# AVR_Roller_PCB_7x.net
KiCad netlist of a schematic drawn in EAGLE
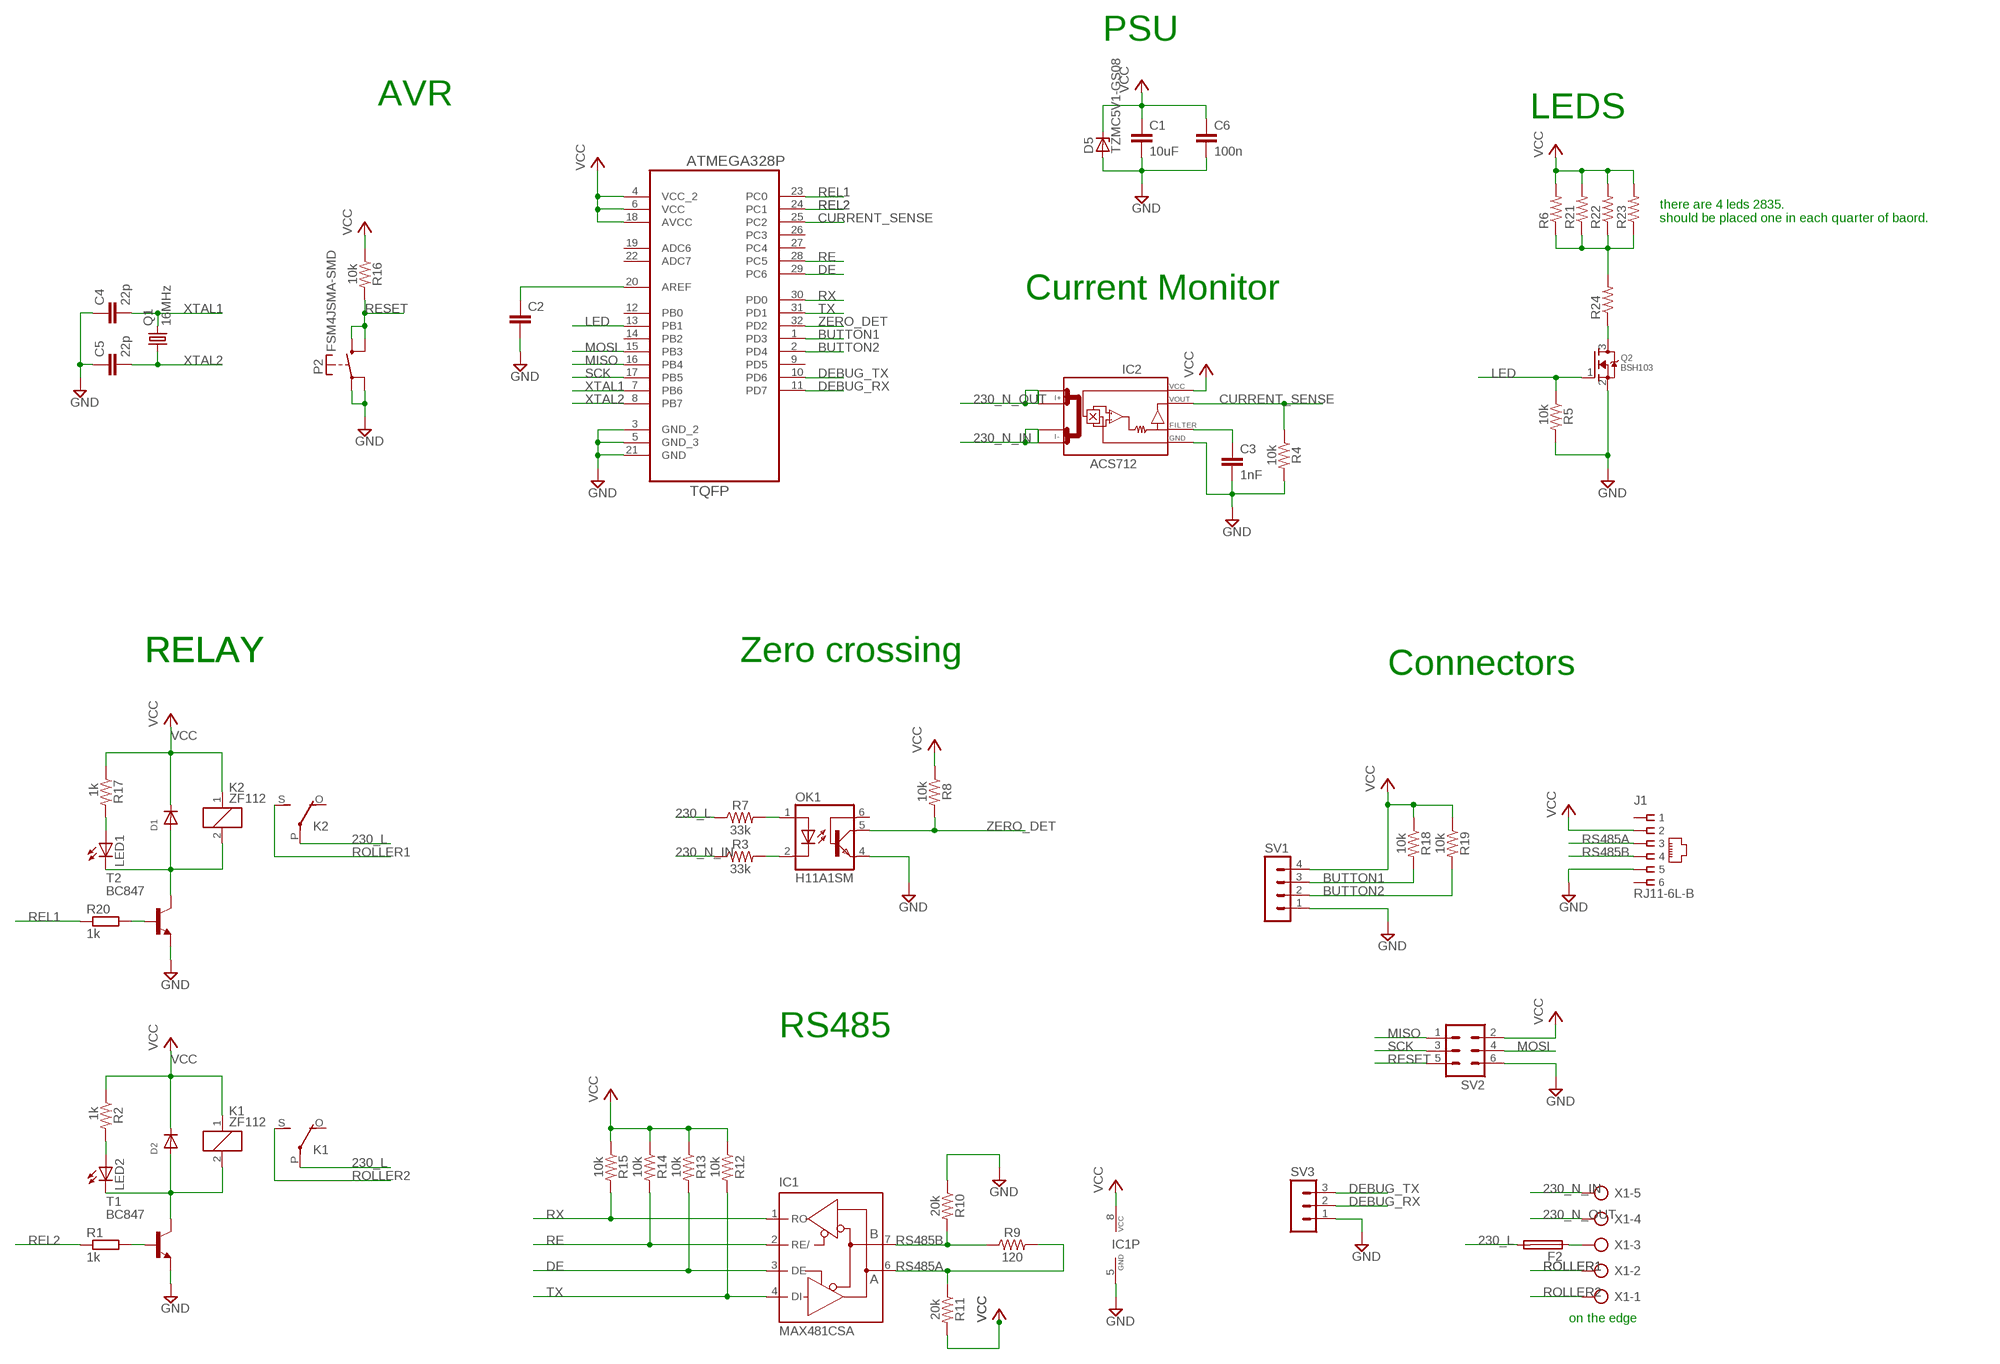
[diagram p0: schematic, sheet 1]

(export (version "E")
  (design (tool "Eeschema 10.0.6"))
  (components
    (comp (ref "C1")
      (value "10uF")
      (footprint "eagle-import:1206")
      (libsource (lib "eagle-import") (part "10UF-1206-6.3V-20%"))
    )
    (comp (ref "C2")
      (value "C-EUC0805K")
      (footprint "eagle-import:C0805K")
      (libsource (lib "eagle-import") (part "C-EUC0805K"))
    )
    (comp (ref "C3")
      (value "1nF")
      (footprint "eagle-import:C0805K")
      (libsource (lib "eagle-import") (part "C-EUC0805K"))
    )
    (comp (ref "C4")
      (value "22p")
      (footprint "eagle-import:C0805K")
      (libsource (lib "eagle-import") (part "C-EUC0805K"))
    )
    (comp (ref "C5")
      (value "22p")
      (footprint "eagle-import:C0805K")
      (libsource (lib "eagle-import") (part "C-EUC0805K"))
    )
    (comp (ref "C6")
      (value "100n")
      (footprint "eagle-import:C0805K")
      (libsource (lib "eagle-import") (part "C-EUC0805K"))
    )
    (comp (ref "D1")
      (value "DIODE_SOD-123FL")
      (footprint "eagle-import:SOD-123FL")
      (libsource (lib "eagle-import") (part "DIODE_SOD-123FL"))
    )
    (comp (ref "D2")
      (value "DIODE_SOD-123FL")
      (footprint "eagle-import:SOD-123FL")
      (libsource (lib "eagle-import") (part "DIODE_SOD-123FL"))
    )
    (comp (ref "D5")
      (value "TZMC5V1-GS08")
      (footprint "eagle-import:SOD80C")
      (libsource (lib "eagle-import") (part "ZENER-DIODESOD80C"))
    )
    (comp (ref "F2")
      (value "TE5")
      (footprint "eagle-import:TE5")
      (libsource (lib "eagle-import") (part "TE5"))
    )
    (comp (ref "IC1")
      (value "MAX481CSA")
      (footprint "eagle-import:SO08")
      (fields (field (name "MF") "MAXIM"))
      (libsource (lib "eagle-import") (part "MAX481CSA"))
    )
    (comp (ref "IC2")
      (value "ACS712")
      (footprint "eagle-import:SO08")
      (libsource (lib "eagle-import") (part "ACS712"))
    )
    (comp (ref "J1")
      (value "RJ11-6L-B")
      (footprint "eagle-import:RJ11-NO_SHIELD")
      (fields (field (name "MF") "TYCO ELECTRONICS"))
      (libsource (lib "eagle-import") (part "RJ11-6L-B"))
    )
    (comp (ref "K1")
      (value "ZF112")
      (footprint "eagle-import:ZF112")
      (libsource (lib "eagle-import") (part "ZF112"))
    )
    (comp (ref "K2")
      (value "ZF112")
      (footprint "eagle-import:ZF112")
      (libsource (lib "eagle-import") (part "ZF112"))
    )
    (comp (ref "LED1")
      (value "LEDCHIPLED_0805")
      (footprint "eagle-import:CHIPLED_0805")
      (libsource (lib "eagle-import") (part "LEDCHIPLED_0805"))
    )
    (comp (ref "LED2")
      (value "LEDCHIPLED_0805")
      (footprint "eagle-import:CHIPLED_0805")
      (libsource (lib "eagle-import") (part "LEDCHIPLED_0805"))
    )
    (comp (ref "OK1")
      (value "H11A1SM")
      (footprint "eagle-import:DIL6-SMD")
      (libsource (lib "eagle-import") (part "H11A?MS1"))
    )
    (comp (ref "P2")
      (value "FSM4JSMA-SMD")
      (footprint "eagle-import:FSM4JSMA-SMD")
      (libsource (lib "eagle-import") (part "FSM4JSMA-SMD"))
    )
    (comp (ref "Q1")
      (value "16MHz")
      (footprint "eagle-import:CSM-7X-DU")
      (libsource (lib "eagle-import") (part "CSM-7X-DU"))
    )
    (comp (ref "Q2")
      (value "BSH103")
      (footprint "eagle-import:SOT23")
      (libsource (lib "eagle-import") (part "MOSFET-NREFLOW"))
    )
    (comp (ref "R1")
      (value "1k")
      (footprint "eagle-import:M0805")
      (libsource (lib "eagle-import") (part "R-EU_M0805"))
    )
    (comp (ref "R2")
      (value "1k")
      (footprint "eagle-import:0805")
      (libsource (lib "eagle-import") (part "RESISTOR0805"))
    )
    (comp (ref "R3")
      (value "33k")
      (footprint "eagle-import:1210")
      (libsource (lib "eagle-import") (part "0.1OHM-1210-1/2W-1%"))
    )
    (comp (ref "R4")
      (value "10k")
      (footprint "eagle-import:0805")
      (libsource (lib "eagle-import") (part "RESISTOR0805"))
    )
    (comp (ref "R5")
      (value "10k")
      (footprint "eagle-import:0805")
      (libsource (lib "eagle-import") (part "RESISTOR0805"))
    )
    (comp (ref "R6")
      (value "R-US_R1210")
      (footprint "eagle-import:R1210")
      (libsource (lib "eagle-import") (part "R-US_R1210"))
    )
    (comp (ref "R7")
      (value "33k")
      (footprint "eagle-import:1210")
      (libsource (lib "eagle-import") (part "0.1OHM-1210-1/2W-1%"))
    )
    (comp (ref "R8")
      (value "10k")
      (footprint "eagle-import:0805")
      (libsource (lib "eagle-import") (part "RESISTOR0805"))
    )
    (comp (ref "R9")
      (value "120")
      (footprint "eagle-import:0805")
      (libsource (lib "eagle-import") (part "RESISTOR0805"))
    )
    (comp (ref "R10")
      (value "20k")
      (footprint "eagle-import:0805")
      (libsource (lib "eagle-import") (part "RESISTOR0805"))
    )
    (comp (ref "R11")
      (value "20k")
      (footprint "eagle-import:0805")
      (libsource (lib "eagle-import") (part "RESISTOR0805"))
    )
    (comp (ref "R12")
      (value "10k")
      (footprint "eagle-import:0805")
      (libsource (lib "eagle-import") (part "RESISTOR0805"))
    )
    (comp (ref "R13")
      (value "10k")
      (footprint "eagle-import:0805")
      (libsource (lib "eagle-import") (part "RESISTOR0805"))
    )
    (comp (ref "R14")
      (value "10k")
      (footprint "eagle-import:0805")
      (libsource (lib "eagle-import") (part "RESISTOR0805"))
    )
    (comp (ref "R15")
      (value "10k")
      (footprint "eagle-import:0805")
      (libsource (lib "eagle-import") (part "RESISTOR0805"))
    )
    (comp (ref "R16")
      (value "10k")
      (footprint "eagle-import:0805")
      (libsource (lib "eagle-import") (part "RESISTOR0805"))
    )
    (comp (ref "R17")
      (value "1k")
      (footprint "eagle-import:0805")
      (libsource (lib "eagle-import") (part "RESISTOR0805"))
    )
    (comp (ref "R18")
      (value "10k")
      (footprint "eagle-import:0805")
      (libsource (lib "eagle-import") (part "RESISTOR0805"))
    )
    (comp (ref "R19")
      (value "10k")
      (footprint "eagle-import:0805")
      (libsource (lib "eagle-import") (part "RESISTOR0805"))
    )
    (comp (ref "R20")
      (value "1k")
      (footprint "eagle-import:M0805")
      (libsource (lib "eagle-import") (part "R-EU_M0805"))
    )
    (comp (ref "R21")
      (value "R-US_R1210")
      (footprint "eagle-import:R1210")
      (libsource (lib "eagle-import") (part "R-US_R1210"))
    )
    (comp (ref "R22")
      (value "R-US_R1210")
      (footprint "eagle-import:R1210")
      (libsource (lib "eagle-import") (part "R-US_R1210"))
    )
    (comp (ref "R23")
      (value "R-US_R1210")
      (footprint "eagle-import:R1210")
      (libsource (lib "eagle-import") (part "R-US_R1210"))
    )
    (comp (ref "R24")
      (value "R-US_R1210")
      (footprint "eagle-import:R1210")
      (libsource (lib "eagle-import") (part "R-US_R1210"))
    )
    (comp (ref "SV1")
      (value "MA04-1")
      (footprint "eagle-import:MA04-1")
      (libsource (lib "eagle-import") (part "MA04-1"))
    )
    (comp (ref "SV2")
      (value "MA03-2")
      (footprint "eagle-import:MA03-2")
      (libsource (lib "eagle-import") (part "MA03-2"))
    )
    (comp (ref "SV3")
      (value "MA03-1")
      (footprint "eagle-import:MA03-1")
      (libsource (lib "eagle-import") (part "MA03-1"))
    )
    (comp (ref "T1")
      (value "BC847")
      (footprint "eagle-import:SOT23")
      (libsource (lib "eagle-import") (part "BC847"))
    )
    (comp (ref "T2")
      (value "BC847")
      (footprint "eagle-import:SOT23")
      (libsource (lib "eagle-import") (part "BC847"))
    )
    (comp (ref "U1")
      (value "ATMEGA328P-AU")
      (footprint "eagle-import:QFP80P900X900X120-32N")
      (libsource (lib "eagle-import") (part "ATMEGA328P-AU"))
    )
    (comp (ref "X1")
      (value "AK300/5")
      (footprint "eagle-import:AK300_5")
      (libsource (lib "eagle-import") (part "AK300/5"))
    )
  )
  (nets
    (net (code "1") (name "/230_L") (class "Default")
      (node (ref "F2") (pin "2") (pinfunction "2_2") (pintype "passive"))
      (node (ref "K1") (pin "P") (pinfunction "P_P") (pintype "passive"))
      (node (ref "K2") (pin "P") (pinfunction "P_P") (pintype "passive"))
      (node (ref "R7") (pin "1") (pinfunction "1_1") (pintype "passive"))
    )
    (net (code "2") (name "/230_N_IN") (class "Default")
      (node (ref "IC2") (pin "3") (pinfunction "I-_0_3") (pintype "bidirectional"))
      (node (ref "IC2") (pin "4") (pinfunction "I-_1_4") (pintype "bidirectional"))
      (node (ref "R3") (pin "1") (pinfunction "1_1") (pintype "passive"))
      (node (ref "X1") (pin "5") (pinfunction "KL_5") (pintype "passive"))
    )
    (net (code "3") (name "/230_N_OUT") (class "Default")
      (node (ref "IC2") (pin "1") (pinfunction "I+_0_1") (pintype "bidirectional"))
      (node (ref "IC2") (pin "2") (pinfunction "I+_1_2") (pintype "bidirectional"))
      (node (ref "X1") (pin "4") (pinfunction "KL_4") (pintype "passive"))
    )
    (net (code "4") (name "/BUTTON1") (class "Default")
      (node (ref "R18") (pin "2") (pinfunction "2_2") (pintype "passive"))
      (node (ref "SV1") (pin "3") (pinfunction "3_3") (pintype "passive"))
      (node (ref "U1") (pin "1") (pinfunction "PD3_1") (pintype "bidirectional"))
    )
    (net (code "5") (name "/BUTTON2") (class "Default")
      (node (ref "R19") (pin "2") (pinfunction "2_2") (pintype "passive"))
      (node (ref "SV1") (pin "2") (pinfunction "2_2") (pintype "passive"))
      (node (ref "U1") (pin "2") (pinfunction "PD4_2") (pintype "bidirectional"))
    )
    (net (code "6") (name "/CURRENT_SENSE") (class "Default")
      (node (ref "IC2") (pin "7") (pinfunction "VOUT_7") (pintype "output"))
      (node (ref "R4") (pin "1") (pinfunction "1_1") (pintype "passive"))
      (node (ref "U1") (pin "25") (pinfunction "PC2_25") (pintype "bidirectional"))
    )
    (net (code "7") (name "/DE") (class "Default")
      (node (ref "IC1") (pin "3") (pinfunction "DE_3") (pintype "input"))
      (node (ref "R13") (pin "2") (pinfunction "2_2") (pintype "passive"))
      (node (ref "U1") (pin "29") (pinfunction "PC6_29") (pintype "bidirectional"))
    )
    (net (code "8") (name "/DEBUG_RX") (class "Default")
      (node (ref "SV3") (pin "2") (pinfunction "2_2") (pintype "passive"))
      (node (ref "U1") (pin "11") (pinfunction "PD7_11") (pintype "bidirectional"))
    )
    (net (code "9") (name "/DEBUG_TX") (class "Default")
      (node (ref "SV3") (pin "3") (pinfunction "3_3") (pintype "passive"))
      (node (ref "U1") (pin "10") (pinfunction "PD6_10") (pintype "bidirectional"))
    )
    (net (code "10") (name "/LED") (class "Default")
      (node (ref "Q2") (pin "1") (pinfunction "G_1") (pintype "bidirectional"))
      (node (ref "R5") (pin "1") (pinfunction "1_1") (pintype "passive"))
      (node (ref "U1") (pin "13") (pinfunction "PB1_13") (pintype "bidirectional"))
    )
    (net (code "11") (name "/MISO") (class "Default")
      (node (ref "SV2") (pin "1") (pinfunction "1_1") (pintype "passive"))
      (node (ref "U1") (pin "16") (pinfunction "PB4_16") (pintype "bidirectional"))
    )
    (net (code "12") (name "/MOSI") (class "Default")
      (node (ref "SV2") (pin "4") (pinfunction "4_4") (pintype "passive"))
      (node (ref "U1") (pin "15") (pinfunction "PB3_15") (pintype "bidirectional"))
    )
    (net (code "13") (name "/RE") (class "Default")
      (node (ref "IC1") (pin "2") (pinfunction "RE/_2") (pintype "input"))
      (node (ref "R14") (pin "2") (pinfunction "2_2") (pintype "passive"))
      (node (ref "U1") (pin "28") (pinfunction "PC5_28") (pintype "bidirectional"))
    )
    (net (code "14") (name "/REL1") (class "Default")
      (node (ref "R20") (pin "1") (pinfunction "1_1") (pintype "passive"))
      (node (ref "U1") (pin "23") (pinfunction "PC0_23") (pintype "bidirectional"))
    )
    (net (code "15") (name "/REL2") (class "Default")
      (node (ref "R1") (pin "1") (pinfunction "1_1") (pintype "passive"))
      (node (ref "U1") (pin "24") (pinfunction "PC1_24") (pintype "bidirectional"))
    )
    (net (code "16") (name "/RESET") (class "Default")
      (node (ref "P2") (pin "P$3") (pinfunction "S_P$3") (pintype "passive"))
      (node (ref "P2") (pin "P$4") (pinfunction "S_P$4") (pintype "passive"))
      (node (ref "R16") (pin "2") (pinfunction "2_2") (pintype "passive"))
      (node (ref "SV2") (pin "5") (pinfunction "5_5") (pintype "passive"))
    )
    (net (code "17") (name "/ROLLER1") (class "Default")
      (node (ref "K2") (pin "S") (pinfunction "S_S") (pintype "passive"))
      (node (ref "X1") (pin "2") (pinfunction "KL_2") (pintype "passive"))
    )
    (net (code "18") (name "/ROLLER2") (class "Default")
      (node (ref "K1") (pin "S") (pinfunction "S_S") (pintype "passive"))
      (node (ref "X1") (pin "1") (pinfunction "KL_1") (pintype "passive"))
    )
    (net (code "19") (name "/RS485A") (class "Default")
      (node (ref "IC1") (pin "6") (pinfunction "A_6") (pintype "passive"))
      (node (ref "J1") (pin "3") (pinfunction "3_3") (pintype "passive"))
      (node (ref "R11") (pin "1") (pinfunction "1_1") (pintype "passive"))
      (node (ref "R9") (pin "2") (pinfunction "2_2") (pintype "passive"))
    )
    (net (code "20") (name "/RS485B") (class "Default")
      (node (ref "IC1") (pin "7") (pinfunction "B_7") (pintype "passive"))
      (node (ref "J1") (pin "4") (pinfunction "4_4") (pintype "passive"))
      (node (ref "R10") (pin "2") (pinfunction "2_2") (pintype "passive"))
      (node (ref "R9") (pin "1") (pinfunction "1_1") (pintype "passive"))
    )
    (net (code "21") (name "/RX") (class "Default")
      (node (ref "IC1") (pin "1") (pinfunction "RO_1") (pintype "output"))
      (node (ref "R15") (pin "2") (pinfunction "2_2") (pintype "passive"))
      (node (ref "U1") (pin "30") (pinfunction "PD0_30") (pintype "bidirectional"))
    )
    (net (code "22") (name "/SCK") (class "Default")
      (node (ref "SV2") (pin "3") (pinfunction "3_3") (pintype "passive"))
      (node (ref "U1") (pin "17") (pinfunction "PB5_17") (pintype "bidirectional"))
    )
    (net (code "23") (name "/TX") (class "Default")
      (node (ref "IC1") (pin "4") (pinfunction "DI_4") (pintype "input"))
      (node (ref "R12") (pin "2") (pinfunction "2_2") (pintype "passive"))
      (node (ref "U1") (pin "31") (pinfunction "PD1_31") (pintype "bidirectional"))
    )
    (net (code "24") (name "/XTAL1") (class "Default")
      (node (ref "C4") (pin "2") (pinfunction "2_2") (pintype "passive"))
      (node (ref "Q1") (pin "2") (pinfunction "2_2") (pintype "passive"))
      (node (ref "U1") (pin "7") (pinfunction "PB6_7") (pintype "bidirectional"))
    )
    (net (code "25") (name "/XTAL2") (class "Default")
      (node (ref "C5") (pin "2") (pinfunction "2_2") (pintype "passive"))
      (node (ref "Q1") (pin "1") (pinfunction "1_1") (pintype "passive"))
      (node (ref "U1") (pin "8") (pinfunction "PB7_8") (pintype "bidirectional"))
    )
    (net (code "26") (name "/ZERO_DET") (class "Default")
      (node (ref "OK1") (pin "5") (pinfunction "COL_5") (pintype "passive"))
      (node (ref "R8") (pin "2") (pinfunction "2_2") (pintype "passive"))
      (node (ref "U1") (pin "32") (pinfunction "PD2_32") (pintype "bidirectional"))
    )
    (net (code "27") (name "GND") (class "Default")
      (node (ref "C1") (pin "2") (pinfunction "2_2") (pintype "passive"))
      (node (ref "C2") (pin "2") (pinfunction "2_2") (pintype "passive"))
      (node (ref "C3") (pin "2") (pinfunction "2_2") (pintype "passive"))
      (node (ref "C4") (pin "1") (pinfunction "1_1") (pintype "passive"))
      (node (ref "C5") (pin "1") (pinfunction "1_1") (pintype "passive"))
      (node (ref "C6") (pin "2") (pinfunction "2_2") (pintype "passive"))
      (node (ref "D5") (pin "A") (pinfunction "A_A") (pintype "passive"))
      (node (ref "IC1") (pin "5") (pinfunction "GND_5") (pintype "power_in"))
      (node (ref "IC2") (pin "5") (pinfunction "GND_5") (pintype "power_in"))
      (node (ref "J1") (pin "5") (pinfunction "5_5") (pintype "passive"))
      (node (ref "OK1") (pin "4") (pinfunction "EMI_4") (pintype "passive"))
      (node (ref "P2") (pin "P$1") (pinfunction "P_P$1") (pintype "passive"))
      (node (ref "P2") (pin "P$2") (pinfunction "P_P$2") (pintype "passive"))
      (node (ref "Q2") (pin "2") (pinfunction "S_2") (pintype "bidirectional"))
      (node (ref "R10") (pin "1") (pinfunction "1_1") (pintype "passive"))
      (node (ref "R4") (pin "2") (pinfunction "2_2") (pintype "passive"))
      (node (ref "R5") (pin "2") (pinfunction "2_2") (pintype "passive"))
      (node (ref "SV1") (pin "1") (pinfunction "1_1") (pintype "passive"))
      (node (ref "SV2") (pin "6") (pinfunction "6_6") (pintype "passive"))
      (node (ref "SV3") (pin "1") (pinfunction "1_1") (pintype "passive"))
      (node (ref "T1") (pin "2") (pinfunction "E_2") (pintype "passive"))
      (node (ref "T2") (pin "2") (pinfunction "E_2") (pintype "passive"))
      (node (ref "U1") (pin "21") (pinfunction "GND_21") (pintype "passive"))
      (node (ref "U1") (pin "3") (pinfunction "GND_2_3") (pintype "passive"))
      (node (ref "U1") (pin "5") (pinfunction "GND_3_5") (pintype "passive"))
    )
    (net (code "28") (name "Net-(IC2-FILTER)") (class "Default")
      (node (ref "C3") (pin "1") (pinfunction "1_1") (pintype "passive"))
      (node (ref "IC2") (pin "6") (pinfunction "FILTER_6") (pintype "bidirectional"))
    )
    (net (code "29") (name "Net-(LED1-PadA)") (class "Default")
      (node (ref "LED1") (pin "A") (pinfunction "A_A") (pintype "passive"))
      (node (ref "R17") (pin "2") (pinfunction "2_2") (pintype "passive"))
    )
    (net (code "30") (name "Net-(LED2-PadA)") (class "Default")
      (node (ref "LED2") (pin "A") (pinfunction "A_A") (pintype "passive"))
      (node (ref "R2") (pin "2") (pinfunction "2_2") (pintype "passive"))
    )
    (net (code "31") (name "Net-(OK1-A)") (class "Default")
      (node (ref "OK1") (pin "1") (pinfunction "A_1") (pintype "passive"))
      (node (ref "R7") (pin "2") (pinfunction "2_2") (pintype "passive"))
    )
    (net (code "32") (name "Net-(OK1-C)") (class "Default")
      (node (ref "OK1") (pin "2") (pinfunction "C_2") (pintype "passive"))
      (node (ref "R3") (pin "2") (pinfunction "2_2") (pintype "passive"))
    )
    (net (code "33") (name "Net-(Q2-D)") (class "Default")
      (node (ref "Q2") (pin "3") (pinfunction "D_3") (pintype "bidirectional"))
      (node (ref "R24") (pin "1") (pinfunction "1_1") (pintype "passive"))
    )
    (net (code "34") (name "Net-(R21-Pad1)") (class "Default")
      (node (ref "R21") (pin "1") (pinfunction "1_1") (pintype "passive"))
      (node (ref "R22") (pin "1") (pinfunction "1_1") (pintype "passive"))
      (node (ref "R23") (pin "1") (pinfunction "1_1") (pintype "passive"))
      (node (ref "R24") (pin "2") (pinfunction "2_2") (pintype "passive"))
      (node (ref "R6") (pin "1") (pinfunction "1_1") (pintype "passive"))
    )
    (net (code "35") (name "Net-(T1-B)") (class "Default")
      (node (ref "R1") (pin "2") (pinfunction "2_2") (pintype "passive"))
      (node (ref "T1") (pin "1") (pinfunction "B_1") (pintype "passive"))
    )
    (net (code "36") (name "Net-(T1-C)") (class "Default")
      (node (ref "D2") (pin "A") (pinfunction "A_A") (pintype "passive"))
      (node (ref "K1") (pin "2") (pinfunction "2_2") (pintype "passive"))
      (node (ref "LED2") (pin "C") (pinfunction "C_C") (pintype "passive"))
      (node (ref "T1") (pin "3") (pinfunction "C_3") (pintype "passive"))
    )
    (net (code "37") (name "Net-(T2-B)") (class "Default")
      (node (ref "R20") (pin "2") (pinfunction "2_2") (pintype "passive"))
      (node (ref "T2") (pin "1") (pinfunction "B_1") (pintype "passive"))
    )
    (net (code "38") (name "Net-(T2-C)") (class "Default")
      (node (ref "D1") (pin "A") (pinfunction "A_A") (pintype "passive"))
      (node (ref "K2") (pin "2") (pinfunction "2_2") (pintype "passive"))
      (node (ref "LED1") (pin "C") (pinfunction "C_C") (pintype "passive"))
      (node (ref "T2") (pin "3") (pinfunction "C_3") (pintype "passive"))
    )
    (net (code "39") (name "Net-(U1-AREF)") (class "Default")
      (node (ref "C2") (pin "1") (pinfunction "1_1") (pintype "passive"))
      (node (ref "U1") (pin "20") (pinfunction "AREF_20") (pintype "input"))
    )
    (net (code "40") (name "Net-(X1C-KL)") (class "Default")
      (node (ref "F2") (pin "1") (pinfunction "1_1") (pintype "passive"))
      (node (ref "X1") (pin "3") (pinfunction "KL_3") (pintype "passive"))
    )
    (net (code "41") (name "VCC") (class "Default")
      (node (ref "C1") (pin "1") (pinfunction "1_1") (pintype "passive"))
      (node (ref "C6") (pin "1") (pinfunction "1_1") (pintype "passive"))
      (node (ref "D1") (pin "C") (pinfunction "C_C") (pintype "passive"))
      (node (ref "D2") (pin "C") (pinfunction "C_C") (pintype "passive"))
      (node (ref "D5") (pin "C") (pinfunction "C_C") (pintype "passive"))
      (node (ref "IC1") (pin "8") (pinfunction "VCC_8") (pintype "power_in"))
      (node (ref "IC2") (pin "8") (pinfunction "VCC_8") (pintype "power_in"))
      (node (ref "J1") (pin "2") (pinfunction "2_2") (pintype "passive"))
      (node (ref "K1") (pin "1") (pinfunction "1_1") (pintype "passive"))
      (node (ref "K2") (pin "1") (pinfunction "1_1") (pintype "passive"))
      (node (ref "R11") (pin "2") (pinfunction "2_2") (pintype "passive"))
      (node (ref "R12") (pin "1") (pinfunction "1_1") (pintype "passive"))
      (node (ref "R13") (pin "1") (pinfunction "1_1") (pintype "passive"))
      (node (ref "R14") (pin "1") (pinfunction "1_1") (pintype "passive"))
      (node (ref "R15") (pin "1") (pinfunction "1_1") (pintype "passive"))
      (node (ref "R16") (pin "1") (pinfunction "1_1") (pintype "passive"))
      (node (ref "R17") (pin "1") (pinfunction "1_1") (pintype "passive"))
      (node (ref "R18") (pin "1") (pinfunction "1_1") (pintype "passive"))
      (node (ref "R19") (pin "1") (pinfunction "1_1") (pintype "passive"))
      (node (ref "R2") (pin "1") (pinfunction "1_1") (pintype "passive"))
      (node (ref "R21") (pin "2") (pinfunction "2_2") (pintype "passive"))
      (node (ref "R22") (pin "2") (pinfunction "2_2") (pintype "passive"))
      (node (ref "R23") (pin "2") (pinfunction "2_2") (pintype "passive"))
      (node (ref "R6") (pin "2") (pinfunction "2_2") (pintype "passive"))
      (node (ref "R8") (pin "1") (pinfunction "1_1") (pintype "passive"))
      (node (ref "SV1") (pin "4") (pinfunction "4_4") (pintype "passive"))
      (node (ref "SV2") (pin "2") (pinfunction "2_2") (pintype "passive"))
      (node (ref "U1") (pin "18") (pinfunction "AVCC_18") (pintype "power_in"))
      (node (ref "U1") (pin "4") (pinfunction "VCC_2_4") (pintype "power_in"))
      (node (ref "U1") (pin "6") (pinfunction "VCC_6") (pintype "power_in"))
    )
    (net (code "42") (name "unconnected-(J1-Pad1)") (class "Default")
      (node (ref "J1") (pin "1") (pinfunction "1_1") (pintype "passive"))
    )
    (net (code "43") (name "unconnected-(J1-Pad6)") (class "Default")
      (node (ref "J1") (pin "6") (pinfunction "6_6") (pintype "passive"))
    )
    (net (code "44") (name "unconnected-(K1-PadO)") (class "Default")
      (node (ref "K1") (pin "O") (pinfunction "O_O") (pintype "passive"))
    )
    (net (code "45") (name "unconnected-(K2-PadO)") (class "Default")
      (node (ref "K2") (pin "O") (pinfunction "O_O") (pintype "passive"))
    )
    (net (code "46") (name "unconnected-(OK1-BAS-Pad6)") (class "Default")
      (node (ref "OK1") (pin "6") (pinfunction "BAS_6") (pintype "passive"))
    )
    (net (code "47") (name "unconnected-(U1-ADC6-Pad19)") (class "Default")
      (node (ref "U1") (pin "19") (pinfunction "ADC6_19") (pintype "input"))
    )
    (net (code "48") (name "unconnected-(U1-ADC7-Pad22)") (class "Default")
      (node (ref "U1") (pin "22") (pinfunction "ADC7_22") (pintype "input"))
    )
    (net (code "49") (name "unconnected-(U1-PB0-Pad12)") (class "Default")
      (node (ref "U1") (pin "12") (pinfunction "PB0_12") (pintype "bidirectional"))
    )
    (net (code "50") (name "unconnected-(U1-PB2-Pad14)") (class "Default")
      (node (ref "U1") (pin "14") (pinfunction "PB2_14") (pintype "bidirectional"))
    )
    (net (code "51") (name "unconnected-(U1-PC3-Pad26)") (class "Default")
      (node (ref "U1") (pin "26") (pinfunction "PC3_26") (pintype "bidirectional"))
    )
    (net (code "52") (name "unconnected-(U1-PC4-Pad27)") (class "Default")
      (node (ref "U1") (pin "27") (pinfunction "PC4_27") (pintype "bidirectional"))
    )
    (net (code "53") (name "unconnected-(U1-PD5-Pad9)") (class "Default")
      (node (ref "U1") (pin "9") (pinfunction "PD5_9") (pintype "bidirectional"))
    )
  )
)
